# pcd_DRAW.net
KiCad netlist of a schematic drawn in EAGLE
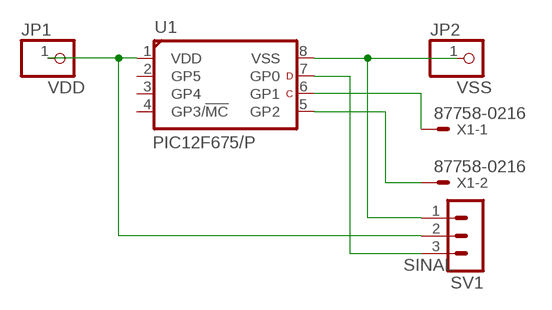
[diagram p0: schematic, sheet 1]

(export (version "E")
  (design (tool "Eeschema 10.0.6"))
  (components
    (comp (ref "JP1")
      (value "PINHD-1X1")
      (footprint "eagle-import:1X01")
      (libsource (lib "eagle-import") (part "PINHD-1X1"))
    )
    (comp (ref "JP2")
      (value "PINHD-1X1")
      (footprint "eagle-import:1X01")
      (libsource (lib "eagle-import") (part "PINHD-1X1"))
    )
    (comp (ref "SV1")
      (value "MA03-1")
      (footprint "eagle-import:MA03-1")
      (libsource (lib "eagle-import") (part "MA03-1"))
    )
    (comp (ref "U1")
      (value "PIC12F675/P")
      (footprint "eagle-import:DIL8-P")
      (libsource (lib "eagle-import") (part "PIC12F675/P"))
    )
    (comp (ref "X1")
      (value "87758-0216")
      (footprint "eagle-import:87758-0216")
      (fields (field (name "MF") "MOLEX"))
      (libsource (lib "eagle-import") (part "87758-0216"))
    )
  )
  (nets
    (net (code "1") (name "/SINAL") (class "Default")
      (node (ref "SV1") (pin "3") (pinfunction "3_3") (pintype "passive"))
      (node (ref "U1") (pin "7") (pinfunction "GP0_7") (pintype "bidirectional"))
    )
    (net (code "2") (name "/VDD") (class "Default")
      (node (ref "JP1") (pin "1") (pinfunction "1_1") (pintype "passive"))
      (node (ref "SV1") (pin "2") (pinfunction "2_2") (pintype "passive"))
      (node (ref "U1") (pin "1") (pinfunction "VDD_1") (pintype "passive"))
    )
    (net (code "3") (name "/VSS") (class "Default")
      (node (ref "JP2") (pin "1") (pinfunction "1_1") (pintype "passive"))
      (node (ref "SV1") (pin "1") (pinfunction "1_1") (pintype "passive"))
      (node (ref "U1") (pin "8") (pinfunction "VSS_8") (pintype "passive"))
    )
    (net (code "4") (name "Net-(U1-GP1)") (class "Default")
      (node (ref "U1") (pin "6") (pinfunction "GP1_6") (pintype "bidirectional"))
      (node (ref "X1") (pin "1") (pinfunction "S_1") (pintype "passive"))
    )
    (net (code "5") (name "Net-(U1-GP2)") (class "Default")
      (node (ref "U1") (pin "5") (pinfunction "GP2_5") (pintype "bidirectional"))
      (node (ref "X1") (pin "2") (pinfunction "S_2") (pintype "passive"))
    )
    (net (code "6") (name "unconnected-(U1-GP3{slash}~{MC}-Pad4)") (class "Default")
      (node (ref "U1") (pin "4") (pinfunction "GP3/~{MC}_4") (pintype "bidirectional"))
    )
    (net (code "7") (name "unconnected-(U1-GP4-Pad3)") (class "Default")
      (node (ref "U1") (pin "3") (pinfunction "GP4_3") (pintype "bidirectional"))
    )
    (net (code "8") (name "unconnected-(U1-GP5-Pad2)") (class "Default")
      (node (ref "U1") (pin "2") (pinfunction "GP5_2") (pintype "bidirectional"))
    )
  )
)
